# SRX-CAN-plugboard.net
KiCad netlist of a schematic drawn in EAGLE
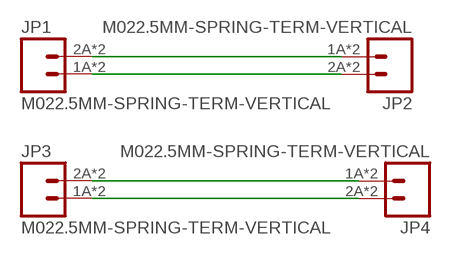
[diagram p0: schematic, sheet 1]

(export (version "E")
  (design (tool "Eeschema 10.0.6"))
  (components
    (comp (ref "JP1")
      (value "M022.5MM-SPRING-TERM-VERTICAL")
      (footprint "eagle-import:1824740000-2X-VERTICAL-SPRING-TERMINAL")
      (libsource (lib "eagle-import") (part "M022.5MM-SPRING-TERM-VERTICAL"))
    )
    (comp (ref "JP2")
      (value "M022.5MM-SPRING-TERM-VERTICAL")
      (footprint "eagle-import:1824740000-2X-VERTICAL-SPRING-TERMINAL")
      (libsource (lib "eagle-import") (part "M022.5MM-SPRING-TERM-VERTICAL"))
    )
    (comp (ref "JP3")
      (value "M022.5MM-SPRING-TERM-VERTICAL")
      (footprint "eagle-import:1824740000-2X-VERTICAL-SPRING-TERMINAL")
      (libsource (lib "eagle-import") (part "M022.5MM-SPRING-TERM-VERTICAL"))
    )
    (comp (ref "JP4")
      (value "M022.5MM-SPRING-TERM-VERTICAL")
      (footprint "eagle-import:1824740000-2X-VERTICAL-SPRING-TERMINAL")
      (libsource (lib "eagle-import") (part "M022.5MM-SPRING-TERM-VERTICAL"))
    )
  )
  (nets
    (net (code "1") (name "Net-(JP1-1-Pad1A)") (class "Default")
      (node (ref "JP1") (pin "1A") (pinfunction "1_1A") (pintype "passive"))
      (node (ref "JP1") (pin "1B") (pinfunction "1_1B") (pintype "passive"))
      (node (ref "JP2") (pin "2A") (pinfunction "2_2A") (pintype "passive"))
      (node (ref "JP2") (pin "2B") (pinfunction "2_2B") (pintype "passive"))
    )
    (net (code "2") (name "Net-(JP1-2-Pad2A)") (class "Default")
      (node (ref "JP1") (pin "2A") (pinfunction "2_2A") (pintype "passive"))
      (node (ref "JP1") (pin "2B") (pinfunction "2_2B") (pintype "passive"))
      (node (ref "JP2") (pin "1A") (pinfunction "1_1A") (pintype "passive"))
      (node (ref "JP2") (pin "1B") (pinfunction "1_1B") (pintype "passive"))
    )
    (net (code "3") (name "Net-(JP3-1-Pad1A)") (class "Default")
      (node (ref "JP3") (pin "1A") (pinfunction "1_1A") (pintype "passive"))
      (node (ref "JP3") (pin "1B") (pinfunction "1_1B") (pintype "passive"))
      (node (ref "JP4") (pin "2A") (pinfunction "2_2A") (pintype "passive"))
      (node (ref "JP4") (pin "2B") (pinfunction "2_2B") (pintype "passive"))
    )
    (net (code "4") (name "Net-(JP3-2-Pad2A)") (class "Default")
      (node (ref "JP3") (pin "2A") (pinfunction "2_2A") (pintype "passive"))
      (node (ref "JP3") (pin "2B") (pinfunction "2_2B") (pintype "passive"))
      (node (ref "JP4") (pin "1A") (pinfunction "1_1A") (pintype "passive"))
      (node (ref "JP4") (pin "1B") (pinfunction "1_1B") (pintype "passive"))
    )
  )
)
